# 8086-_Project.net
KiCad netlist of a schematic drawn in EasyEDA
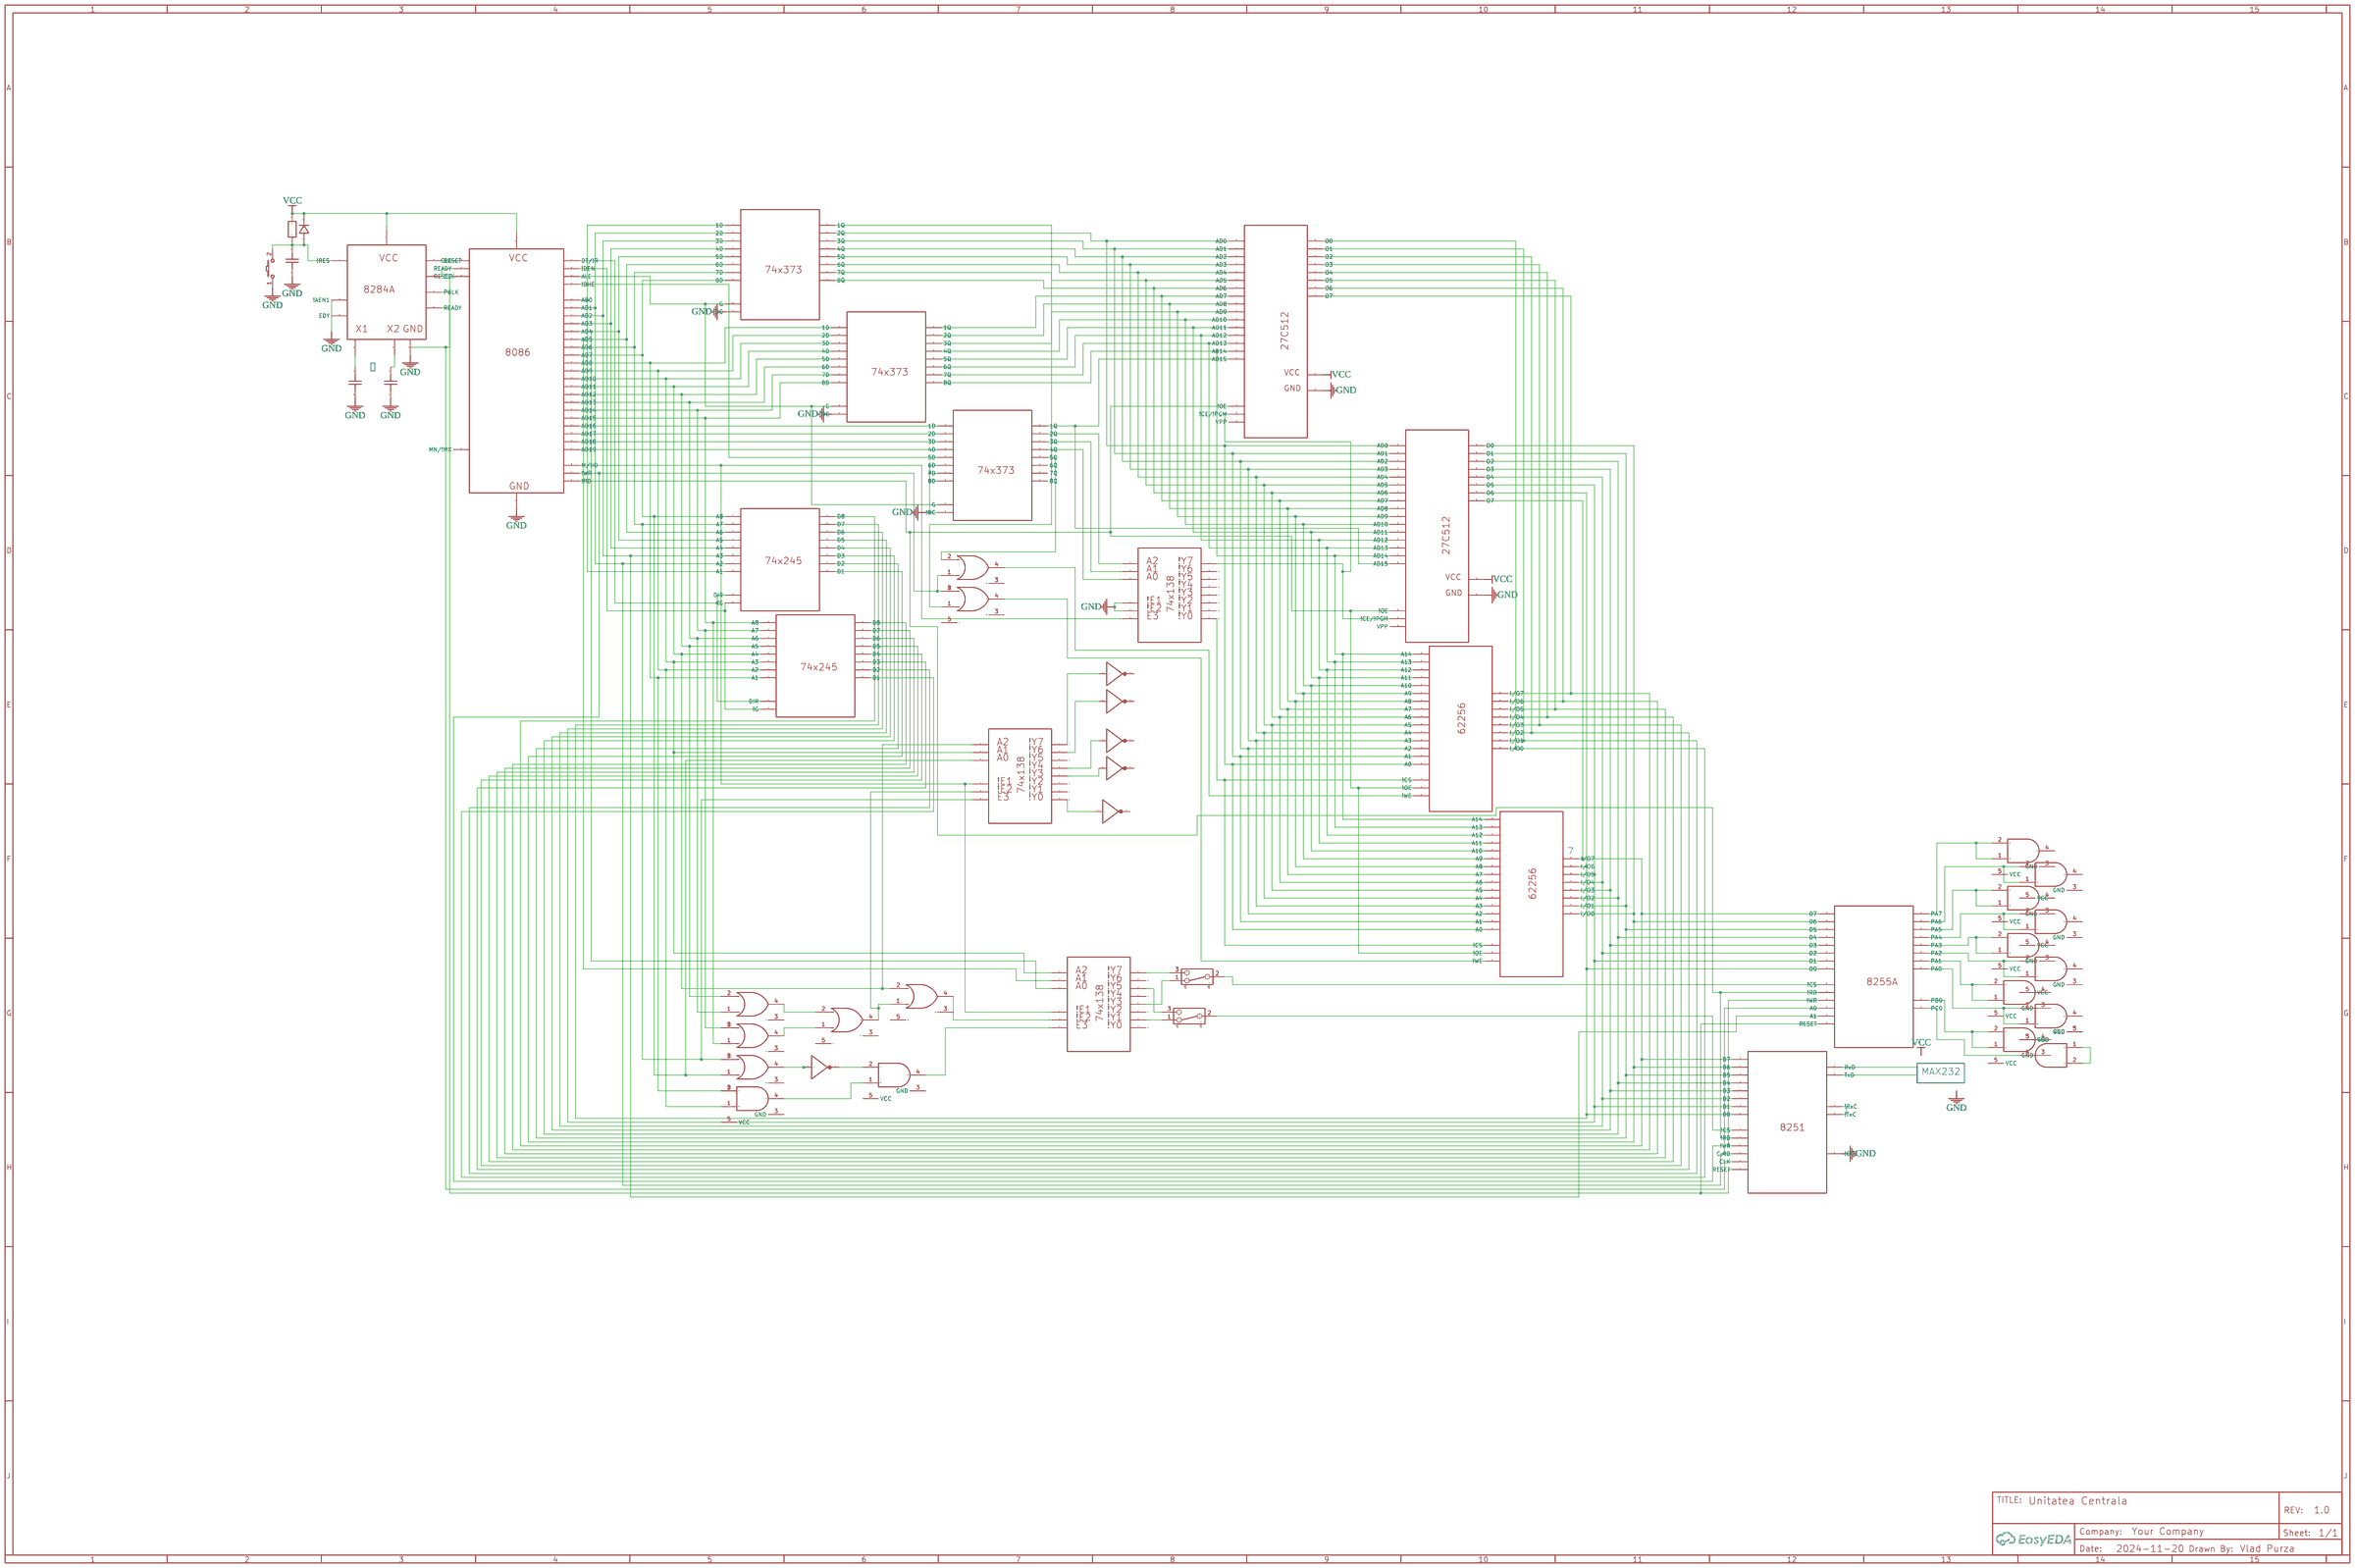
[diagram p0: schematic sheet]

(export (version "E")
  (design (tool "Eeschema 10.0.6"))
  (components
    (comp (ref "C1") (value "0.1u") (libsource (lib "") (part "C_0603_US")))
    (comp (ref "C2") (value "0.1u") (libsource (lib "") (part "C_0805_US")))
    (comp (ref "C3") (value "0.1u") (libsource (lib "") (part "C_0805_US")))
    (comp (ref "D1")
      (value "1N4007W")
      (fields (field (name "Manufacturer") "BLUE ROCKET"))
      (libsource (lib "") (part "1N4007W"))
    )
    (comp (ref "KEY1")
      (value "K2-3.6×6.1_SMD")
      (fields (field (name "Manufacturer Part") "K2-1107ST-A4SW-06"))
      (libsource (lib "") (part "K2-3.6×6.1_SMD"))
    )
    (comp (ref "R1") (value "1k") (libsource (lib "") (part "R_0603_EU")))
    (comp (ref "SW1")
      (value "SK-12D02-VG5")
      (fields (field (name "Manufacturer") "Rectangular Connectors - Contacts"))
      (libsource (lib "") (part "SK-12D02-VG5"))
    )
    (comp (ref "SW2")
      (value "SK-12D02-VG5")
      (fields (field (name "Manufacturer") "Rectangular Connectors - Contacts"))
      (libsource (lib "") (part "SK-12D02-VG5"))
    )
    (comp (ref "U1") (value "8086") (libsource (lib "") (part "8086")))
    (comp (ref "U2") (value "74x373") (libsource (lib "") (part "74x373")))
    (comp (ref "U3") (value "74x245") (libsource (lib "") (part "74x245")))
    (comp (ref "U4") (value "74x245") (libsource (lib "") (part "74x245")))
    (comp (ref "U5") (value "8284A") (libsource (lib "") (part "8284A")))
    (comp (ref "U6") (value "27C512") (libsource (lib "") (part "27C512")))
    (comp (ref "U7") (value "27C512") (libsource (lib "") (part "27C512")))
    (comp (ref "U8") (value "74x373") (libsource (lib "") (part "74x373")))
    (comp (ref "U9") (value "74x373") (libsource (lib "") (part "74x373")))
    (comp (ref "U10") (value "74x138") (libsource (lib "") (part "74x138")))
    (comp (ref "U11") (value "MC74VHC1G32DFT1") (libsource (lib "") (part "MC74VHC1G32DFT1")))
    (comp (ref "U12") (value "MC74VHC1G32DFT1") (libsource (lib "") (part "MC74VHC1G32DFT1")))
    (comp (ref "U13") (value "62256") (libsource (lib "") (part "62256")))
    (comp (ref "U14") (value "62256") (libsource (lib "") (part "62256")))
    (comp (ref "U15") (value "74x138") (libsource (lib "") (part "74x138")))
    (comp (ref "U16") (value "74x138") (libsource (lib "") (part "74x138")))
    (comp (ref "U17") (value "HD74ALVC1G08VS") (libsource (lib "") (part "HD74ALVC1G08VS")))
    (comp (ref "U18") (value "HD74ALVC1G08VS") (libsource (lib "") (part "HD74ALVC1G08VS")))
    (comp (ref "U19") (value "MC74VHC1G32DFT1") (libsource (lib "") (part "MC74VHC1G32DFT1_1")))
    (comp (ref "U20") (value "MC74VHC1G32DFT1") (libsource (lib "") (part "MC74VHC1G32DFT1_1")))
    (comp (ref "U21") (value "MC74VHC1G32DFT1") (libsource (lib "") (part "MC74VHC1G32DFT1_1")))
    (comp (ref "U22") (value "MC74VHC1G32DFT1") (libsource (lib "") (part "MC74VHC1G32DFT1_1")))
    (comp (ref "U23") (value "MC74VHC1G32DFT1") (libsource (lib "") (part "MC74VHC1G32DFT1_1")))
    (comp (ref "U24") (value "NOT Gate") (libsource (lib "") (part "NOT Gate")))
    (comp (ref "U25") (value "NOT Gate") (libsource (lib "") (part "NOT Gate")))
    (comp (ref "U26") (value "NOT Gate") (libsource (lib "") (part "NOT Gate")))
    (comp (ref "U27") (value "NOT Gate") (libsource (lib "") (part "NOT Gate")))
    (comp (ref "U28") (value "NOT Gate") (libsource (lib "") (part "NOT Gate")))
    (comp (ref "U29") (value "NOT Gate") (libsource (lib "") (part "NOT Gate")))
    (comp (ref "U30") (value "8251") (libsource (lib "") (part "8251")))
    (comp (ref "U31") (value "8255A") (libsource (lib "") (part "8255A")))
    (comp (ref "U32") (value "HD74ALVC1G08VS") (libsource (lib "") (part "HD74ALVC1G08VS")))
    (comp (ref "U33") (value "HD74ALVC1G08VS") (libsource (lib "") (part "HD74ALVC1G08VS")))
    (comp (ref "U34") (value "HD74ALVC1G08VS") (libsource (lib "") (part "HD74ALVC1G08VS")))
    (comp (ref "U35") (value "HD74ALVC1G08VS") (libsource (lib "") (part "HD74ALVC1G08VS")))
    (comp (ref "U36") (value "HD74ALVC1G08VS") (libsource (lib "") (part "HD74ALVC1G08VS")))
    (comp (ref "U37") (value "HD74ALVC1G08VS") (libsource (lib "") (part "HD74ALVC1G08VS")))
    (comp (ref "U38") (value "HD74ALVC1G08VS") (libsource (lib "") (part "HD74ALVC1G08VS")))
    (comp (ref "U39") (value "HD74ALVC1G08VS") (libsource (lib "") (part "HD74ALVC1G08VS")))
    (comp (ref "U40") (value "HD74ALVC1G08VS") (libsource (lib "") (part "HD74ALVC1G08VS")))
    (comp (ref "U41") (value "HD74ALVC1G08VS") (libsource (lib "") (part "HD74ALVC1G08VS_1")))
  )
  (nets
    (net (code "1") (name "GND") (class "Default")
      (node (ref "C1") (pin "2") (pinfunction "2_2") (pintype "unspecified"))
      (node (ref "C2") (pin "2") (pinfunction "2_2") (pintype "unspecified"))
      (node (ref "C3") (pin "2") (pinfunction "2_2") (pintype "unspecified"))
      (node (ref "KEY1") (pin "1") (pinfunction "1_1") (pintype "unspecified"))
    )
    (net (code "2") (name "Net-(C1-Pad1)") (class "Default")
      (node (ref "C1") (pin "1") (pinfunction "1_1") (pintype "unspecified"))
      (node (ref "D1") (pin "2") (pinfunction "2_2") (pintype "unspecified"))
      (node (ref "KEY1") (pin "2") (pinfunction "2_2") (pintype "unspecified"))
      (node (ref "R1") (pin "1") (pinfunction "1_1") (pintype "unspecified"))
    )
    (net (code "3") (name "Net-(U11-IN_A)") (class "Default")
      (node (ref "U11") (pin "2") (pinfunction "IN_A_2") (pintype "unspecified"))
      (node (ref "U12") (pin "1") (pinfunction "IN_B_1") (pintype "unspecified"))
      (node (ref "U12") (pin "5") (pinfunction "VDD_5") (pintype "passive"))
    )
    (net (code "4") (name "Net-(U17-IN_A)") (class "Default")
      (node (ref "U17") (pin "2") (pinfunction "IN_A_2") (pintype "unspecified"))
      (node (ref "U24") (pin "2") (pinfunction "OUT_2") (pintype "unspecified"))
    )
    (net (code "5") (name "Net-(U17-IN_B)") (class "Default")
      (node (ref "U17") (pin "1") (pinfunction "IN_B_1") (pintype "unspecified"))
      (node (ref "U18") (pin "4") (pinfunction "OUT_Y_4") (pintype "output"))
    )
    (net (code "6") (name "Net-(U18-IN_A)") (class "Default")
      (node (ref "U18") (pin "2") (pinfunction "IN_A_2") (pintype "unspecified"))
      (node (ref "U19") (pin "5") (pinfunction "VDD_5") (pintype "passive"))
    )
    (net (code "7") (name "Net-(U19-IN_A)") (class "Default")
      (node (ref "U19") (pin "2") (pinfunction "IN_A_2") (pintype "unspecified"))
      (node (ref "U20") (pin "5") (pinfunction "VDD_5") (pintype "passive"))
    )
    (net (code "8") (name "Net-(U19-Y)") (class "Default")
      (node (ref "U19") (pin "4") (pinfunction "Y_4") (pintype "output"))
      (node (ref "U24") (pin "1") (pinfunction "IN_1") (pintype "unspecified"))
    )
    (net (code "9") (name "Net-(U20-IN_A)") (class "Default")
      (node (ref "U20") (pin "2") (pinfunction "IN_A_2") (pintype "unspecified"))
      (node (ref "U21") (pin "5") (pinfunction "VDD_5") (pintype "passive"))
    )
    (net (code "10") (name "Net-(U20-Y)") (class "Default")
      (node (ref "U20") (pin "4") (pinfunction "Y_4") (pintype "output"))
      (node (ref "U22") (pin "1") (pinfunction "IN_B_1") (pintype "unspecified"))
    )
    (net (code "11") (name "Net-(U21-Y)") (class "Default")
      (node (ref "U21") (pin "4") (pinfunction "Y_4") (pintype "output"))
      (node (ref "U22") (pin "2") (pinfunction "IN_A_2") (pintype "unspecified"))
    )
    (net (code "12") (name "Net-(U22-Y)") (class "Default")
      (node (ref "U22") (pin "4") (pinfunction "Y_4") (pintype "output"))
      (node (ref "U23") (pin "1") (pinfunction "IN_B_1") (pintype "unspecified"))
    )
    (net (code "13") (name "Net-(U32-IN_A)") (class "Default")
      (node (ref "U32") (pin "1") (pinfunction "IN_B_1") (pintype "unspecified"))
      (node (ref "U32") (pin "2") (pinfunction "IN_A_2") (pintype "unspecified"))
    )
    (net (code "14") (name "Net-(U33-IN_A)") (class "Default")
      (node (ref "U33") (pin "1") (pinfunction "IN_B_1") (pintype "unspecified"))
      (node (ref "U33") (pin "2") (pinfunction "IN_A_2") (pintype "unspecified"))
    )
    (net (code "15") (name "Net-(U34-IN_A)") (class "Default")
      (node (ref "U34") (pin "1") (pinfunction "IN_B_1") (pintype "unspecified"))
      (node (ref "U34") (pin "2") (pinfunction "IN_A_2") (pintype "unspecified"))
    )
    (net (code "16") (name "Net-(U35-IN_A)") (class "Default")
      (node (ref "U35") (pin "1") (pinfunction "IN_B_1") (pintype "unspecified"))
      (node (ref "U35") (pin "2") (pinfunction "IN_A_2") (pintype "unspecified"))
    )
    (net (code "17") (name "Net-(U36-IN_A)") (class "Default")
      (node (ref "U36") (pin "1") (pinfunction "IN_B_1") (pintype "unspecified"))
      (node (ref "U36") (pin "2") (pinfunction "IN_A_2") (pintype "unspecified"))
    )
    (net (code "18") (name "Net-(U37-IN_A)") (class "Default")
      (node (ref "U37") (pin "1") (pinfunction "IN_B_1") (pintype "unspecified"))
      (node (ref "U37") (pin "2") (pinfunction "IN_A_2") (pintype "unspecified"))
    )
    (net (code "19") (name "Net-(U38-IN_A)") (class "Default")
      (node (ref "U38") (pin "1") (pinfunction "IN_B_1") (pintype "unspecified"))
      (node (ref "U38") (pin "2") (pinfunction "IN_A_2") (pintype "unspecified"))
    )
    (net (code "20") (name "Net-(U39-GND)") (class "Default")
      (node (ref "U39") (pin "3") (pinfunction "GND_3") (pintype "passive"))
      (node (ref "U41") (pin "5") (pinfunction "VCC_5") (pintype "passive"))
    )
    (net (code "21") (name "Net-(U39-IN_A)") (class "Default")
      (node (ref "U39") (pin "1") (pinfunction "IN_B_1") (pintype "unspecified"))
      (node (ref "U39") (pin "2") (pinfunction "IN_A_2") (pintype "unspecified"))
    )
    (net (code "22") (name "Net-(U39-VCC)") (class "Default")
      (node (ref "U39") (pin "5") (pinfunction "VCC_5") (pintype "passive"))
      (node (ref "U41") (pin "3") (pinfunction "GND_3") (pintype "passive"))
    )
    (net (code "23") (name "Net-(U40-IN_A)") (class "Default")
      (node (ref "U40") (pin "1") (pinfunction "IN_B_1") (pintype "unspecified"))
      (node (ref "U40") (pin "2") (pinfunction "IN_A_2") (pintype "unspecified"))
    )
    (net (code "24") (name "Net-(U41-IN_A)") (class "Default")
      (node (ref "U41") (pin "1") (pinfunction "IN_B_1") (pintype "unspecified"))
      (node (ref "U41") (pin "2") (pinfunction "IN_A_2") (pintype "unspecified"))
    )
    (net (code "25") (name "VCC") (class "Default")
      (node (ref "D1") (pin "1") (pinfunction "1_1") (pintype "unspecified"))
      (node (ref "R1") (pin "2") (pinfunction "2_2") (pintype "unspecified"))
    )
    (net (code "26") (name "unconnected-(C2-Pad1)") (class "Default")
      (node (ref "C2") (pin "1") (pinfunction "1_1") (pintype "unspecified"))
    )
    (net (code "27") (name "unconnected-(C3-Pad1)") (class "Default")
      (node (ref "C3") (pin "1") (pinfunction "1_1") (pintype "unspecified"))
    )
    (net (code "28") (name "unconnected-(SW1-Pad1)") (class "Default")
      (node (ref "SW1") (pin "1") (pinfunction "1_1") (pintype "unspecified"))
    )
    (net (code "29") (name "unconnected-(SW1-Pad2)") (class "Default")
      (node (ref "SW1") (pin "2") (pinfunction "2_2") (pintype "unspecified"))
    )
    (net (code "30") (name "unconnected-(SW1-Pad3)") (class "Default")
      (node (ref "SW1") (pin "3") (pinfunction "3_3") (pintype "unspecified"))
    )
    (net (code "31") (name "unconnected-(SW1-Pad4)") (class "Default")
      (node (ref "SW1") (pin "4") (pinfunction "4_4") (pintype "unspecified"))
    )
    (net (code "32") (name "unconnected-(SW1-Pad5)") (class "Default")
      (node (ref "SW1") (pin "5") (pinfunction "5_5") (pintype "unspecified"))
    )
    (net (code "33") (name "unconnected-(SW2-Pad1)") (class "Default")
      (node (ref "SW2") (pin "1") (pinfunction "1_1") (pintype "unspecified"))
    )
    (net (code "34") (name "unconnected-(SW2-Pad2)") (class "Default")
      (node (ref "SW2") (pin "2") (pinfunction "2_2") (pintype "unspecified"))
    )
    (net (code "35") (name "unconnected-(SW2-Pad3)") (class "Default")
      (node (ref "SW2") (pin "3") (pinfunction "3_3") (pintype "unspecified"))
    )
    (net (code "36") (name "unconnected-(SW2-Pad4)") (class "Default")
      (node (ref "SW2") (pin "4") (pinfunction "4_4") (pintype "unspecified"))
    )
    (net (code "37") (name "unconnected-(SW2-Pad5)") (class "Default")
      (node (ref "SW2") (pin "5") (pinfunction "5_5") (pintype "unspecified"))
    )
    (net (code "38") (name "unconnected-(U1-!BHE-Pad23)") (class "Default")
      (node (ref "U1") (pin "23") (pinfunction "!BHE_23") (pintype "unspecified"))
    )
    (net (code "39") (name "unconnected-(U1-!DEN-Pad21)") (class "Default")
      (node (ref "U1") (pin "21") (pinfunction "!DEN_21") (pintype "unspecified"))
    )
    (net (code "40") (name "unconnected-(U1-!RD-Pad30)") (class "Default")
      (node (ref "U1") (pin "30") (pinfunction "!RD_30") (pintype "unspecified"))
    )
    (net (code "41") (name "unconnected-(U1-!WR-Pad29)") (class "Default")
      (node (ref "U1") (pin "29") (pinfunction "!WR_29") (pintype "unspecified"))
    )
    (net (code "42") (name "unconnected-(U1-20-Pad31)") (class "Default")
      (node (ref "U1") (pin "31") (pinfunction "20_31") (pintype "unspecified"))
    )
    (net (code "43") (name "unconnected-(U1-21-Pad32)") (class "Default")
      (node (ref "U1") (pin "32") (pinfunction "21_32") (pintype "unspecified"))
    )
    (net (code "44") (name "unconnected-(U1-AD0-Pad0)") (class "Default")
      (node (ref "U1") (pin "0") (pinfunction "AD0_0") (pintype "unspecified"))
    )
    (net (code "45") (name "unconnected-(U1-AD1-Pad1)") (class "Default")
      (node (ref "U1") (pin "1") (pinfunction "AD1_1") (pintype "unspecified"))
    )
    (net (code "46") (name "unconnected-(U1-AD2-Pad2)") (class "Default")
      (node (ref "U1") (pin "2") (pinfunction "AD2_2") (pintype "unspecified"))
    )
    (net (code "47") (name "unconnected-(U1-AD3-Pad3)") (class "Default")
      (node (ref "U1") (pin "3") (pinfunction "AD3_3") (pintype "unspecified"))
    )
    (net (code "48") (name "unconnected-(U1-AD4-Pad4)") (class "Default")
      (node (ref "U1") (pin "4") (pinfunction "AD4_4") (pintype "unspecified"))
    )
    (net (code "49") (name "unconnected-(U1-AD5-Pad5)") (class "Default")
      (node (ref "U1") (pin "5") (pinfunction "AD5_5") (pintype "unspecified"))
    )
    (net (code "50") (name "unconnected-(U1-AD6-Pad6)") (class "Default")
      (node (ref "U1") (pin "6") (pinfunction "AD6_6") (pintype "unspecified"))
    )
    (net (code "51") (name "unconnected-(U1-AD7-Pad7)") (class "Default")
      (node (ref "U1") (pin "7") (pinfunction "AD7_7") (pintype "unspecified"))
    )
    (net (code "52") (name "unconnected-(U1-AD8-Pad8)") (class "Default")
      (node (ref "U1") (pin "8") (pinfunction "AD8_8") (pintype "unspecified"))
    )
    (net (code "53") (name "unconnected-(U1-AD9-Pad9)") (class "Default")
      (node (ref "U1") (pin "9") (pinfunction "AD9_9") (pintype "unspecified"))
    )
    (net (code "54") (name "unconnected-(U1-AD10-Pad10)") (class "Default")
      (node (ref "U1") (pin "10") (pinfunction "AD10_10") (pintype "unspecified"))
    )
    (net (code "55") (name "unconnected-(U1-AD11-Pad11)") (class "Default")
      (node (ref "U1") (pin "11") (pinfunction "AD11_11") (pintype "unspecified"))
    )
    (net (code "56") (name "unconnected-(U1-AD12-Pad12)") (class "Default")
      (node (ref "U1") (pin "12") (pinfunction "AD12_12") (pintype "unspecified"))
    )
    (net (code "57") (name "unconnected-(U1-AD13-Pad13)") (class "Default")
      (node (ref "U1") (pin "13") (pinfunction "AD13_13") (pintype "unspecified"))
    )
    (net (code "58") (name "unconnected-(U1-AD14-Pad14)") (class "Default")
      (node (ref "U1") (pin "14") (pinfunction "AD14_14") (pintype "unspecified"))
    )
    (net (code "59") (name "unconnected-(U1-AD15-Pad15)") (class "Default")
      (node (ref "U1") (pin "15") (pinfunction "AD15_15") (pintype "unspecified"))
    )
    (net (code "60") (name "unconnected-(U1-AD16-Pad16)") (class "Default")
      (node (ref "U1") (pin "16") (pinfunction "AD16_16") (pintype "unspecified"))
    )
    (net (code "61") (name "unconnected-(U1-AD17-Pad17)") (class "Default")
      (node (ref "U1") (pin "17") (pinfunction "AD17_17") (pintype "unspecified"))
    )
    (net (code "62") (name "unconnected-(U1-AD18-Pad18)") (class "Default")
      (node (ref "U1") (pin "18") (pinfunction "AD18_18") (pintype "unspecified"))
    )
    (net (code "63") (name "unconnected-(U1-AD19-Pad19)") (class "Default")
      (node (ref "U1") (pin "19") (pinfunction "AD19_19") (pintype "unspecified"))
    )
    (net (code "64") (name "unconnected-(U1-ALE-Pad22)") (class "Default")
      (node (ref "U1") (pin "22") (pinfunction "ALE_22") (pintype "unspecified"))
    )
    (net (code "65") (name "unconnected-(U1-CLK-Pad24)") (class "Default")
      (node (ref "U1") (pin "24") (pinfunction "CLK_24") (pintype "unspecified"))
    )
    (net (code "66") (name "unconnected-(U1-DT{slash}!R-Pad20)") (class "Default")
      (node (ref "U1") (pin "20") (pinfunction "DT/!R_20") (pintype "unspecified"))
    )
    (net (code "67") (name "unconnected-(U1-MN{slash}!MX-Pad27)") (class "Default")
      (node (ref "U1") (pin "27") (pinfunction "MN/!MX_27") (pintype "unspecified"))
    )
    (net (code "68") (name "unconnected-(U1-M{slash}!IO-Pad28)") (class "Default")
      (node (ref "U1") (pin "28") (pinfunction "M/!IO_28") (pintype "unspecified"))
    )
    (net (code "69") (name "unconnected-(U1-READY-Pad25)") (class "Default")
      (node (ref "U1") (pin "25") (pinfunction "READY_25") (pintype "unspecified"))
    )
    (net (code "70") (name "unconnected-(U1-RESET-Pad26)") (class "Default")
      (node (ref "U1") (pin "26") (pinfunction "RESET_26") (pintype "unspecified"))
    )
    (net (code "71") (name "unconnected-(U2-!OC-Pad21)") (class "Default")
      (node (ref "U2") (pin "21") (pinfunction "!OC_21") (pintype "unspecified"))
    )
    (net (code "72") (name "unconnected-(U2-1D-Pad1)") (class "Default")
      (node (ref "U2") (pin "1") (pinfunction "1D_1") (pintype "unspecified"))
    )
    (net (code "73") (name "unconnected-(U2-1Q-Pad9)") (class "Default")
      (node (ref "U2") (pin "9") (pinfunction "1Q_9") (pintype "unspecified"))
    )
    (net (code "74") (name "unconnected-(U2-2D-Pad2)") (class "Default")
      (node (ref "U2") (pin "2") (pinfunction "2D_2") (pintype "unspecified"))
    )
    (net (code "75") (name "unconnected-(U2-2Q-Pad10)") (class "Default")
      (node (ref "U2") (pin "10") (pinfunction "2Q_10") (pintype "unspecified"))
    )
    (net (code "76") (name "unconnected-(U2-3D-Pad3)") (class "Default")
      (node (ref "U2") (pin "3") (pinfunction "3D_3") (pintype "unspecified"))
    )
    (net (code "77") (name "unconnected-(U2-3Q-Pad11)") (class "Default")
      (node (ref "U2") (pin "11") (pinfunction "3Q_11") (pintype "unspecified"))
    )
    (net (code "78") (name "unconnected-(U2-4D-Pad4)") (class "Default")
      (node (ref "U2") (pin "4") (pinfunction "4D_4") (pintype "unspecified"))
    )
    (net (code "79") (name "unconnected-(U2-4Q-Pad12)") (class "Default")
      (node (ref "U2") (pin "12") (pinfunction "4Q_12") (pintype "unspecified"))
    )
    (net (code "80") (name "unconnected-(U2-5D-Pad5)") (class "Default")
      (node (ref "U2") (pin "5") (pinfunction "5D_5") (pintype "unspecified"))
    )
    (net (code "81") (name "unconnected-(U2-5Q-Pad16)") (class "Default")
      (node (ref "U2") (pin "16") (pinfunction "5Q_16") (pintype "unspecified"))
    )
    (net (code "82") (name "unconnected-(U2-6D-Pad6)") (class "Default")
      (node (ref "U2") (pin "6") (pinfunction "6D_6") (pintype "unspecified"))
    )
    (net (code "83") (name "unconnected-(U2-6Q-Pad13)") (class "Default")
      (node (ref "U2") (pin "13") (pinfunction "6Q_13") (pintype "unspecified"))
    )
    (net (code "84") (name "unconnected-(U2-7D-Pad7)") (class "Default")
      (node (ref "U2") (pin "7") (pinfunction "7D_7") (pintype "unspecified"))
    )
    (net (code "85") (name "unconnected-(U2-7Q-Pad14)") (class "Default")
      (node (ref "U2") (pin "14") (pinfunction "7Q_14") (pintype "unspecified"))
    )
    (net (code "86") (name "unconnected-(U2-8D-Pad8)") (class "Default")
      (node (ref "U2") (pin "8") (pinfunction "8D_8") (pintype "unspecified"))
    )
    (net (code "87") (name "unconnected-(U2-8Q-Pad15)") (class "Default")
      (node (ref "U2") (pin "15") (pinfunction "8Q_15") (pintype "unspecified"))
    )
    (net (code "88") (name "unconnected-(U2-G-Pad20)") (class "Default")
      (node (ref "U2") (pin "20") (pinfunction "G_20") (pintype "unspecified"))
    )
    (net (code "89") (name "unconnected-(U3-!G-Pad21)") (class "Default")
      (node (ref "U3") (pin "21") (pinfunction "!G_21") (pintype "unspecified"))
    )
    (net (code "90") (name "unconnected-(U3-A1-Pad8)") (class "Default")
      (node (ref "U3") (pin "8") (pinfunction "A1_8") (pintype "unspecified"))
    )
    (net (code "91") (name "unconnected-(U3-A2-Pad7)") (class "Default")
      (node (ref "U3") (pin "7") (pinfunction "A2_7") (pintype "unspecified"))
    )
    (net (code "92") (name "unconnected-(U3-A3-Pad6)") (class "Default")
      (node (ref "U3") (pin "6") (pinfunction "A3_6") (pintype "unspecified"))
    )
    (net (code "93") (name "unconnected-(U3-A4-Pad5)") (class "Default")
      (node (ref "U3") (pin "5") (pinfunction "A4_5") (pintype "unspecified"))
    )
    (net (code "94") (name "unconnected-(U3-A5-Pad4)") (class "Default")
      (node (ref "U3") (pin "4") (pinfunction "A5_4") (pintype "unspecified"))
    )
    (net (code "95") (name "unconnected-(U3-A6-Pad3)") (class "Default")
      (node (ref "U3") (pin "3") (pinfunction "A6_3") (pintype "unspecified"))
    )
    (net (code "96") (name "unconnected-(U3-A7-Pad2)") (class "Default")
      (node (ref "U3") (pin "2") (pinfunction "A7_2") (pintype "unspecified"))
    )
    (net (code "97") (name "unconnected-(U3-A8-Pad1)") (class "Default")
      (node (ref "U3") (pin "1") (pinfunction "A8_1") (pintype "unspecified"))
    )
    (net (code "98") (name "unconnected-(U3-D1-Pad15)") (class "Default")
      (node (ref "U3") (pin "15") (pinfunction "D1_15") (pintype "unspecified"))
    )
    (net (code "99") (name "unconnected-(U3-D2-Pad14)") (class "Default")
      (node (ref "U3") (pin "14") (pinfunction "D2_14") (pintype "unspecified"))
    )
    (net (code "100") (name "unconnected-(U3-D3-Pad13)") (class "Default")
      (node (ref "U3") (pin "13") (pinfunction "D3_13") (pintype "unspecified"))
    )
    (net (code "101") (name "unconnected-(U3-D4-Pad16)") (class "Default")
      (node (ref "U3") (pin "16") (pinfunction "D4_16") (pintype "unspecified"))
    )
    (net (code "102") (name "unconnected-(U3-D5-Pad12)") (class "Default")
      (node (ref "U3") (pin "12") (pinfunction "D5_12") (pintype "unspecified"))
    )
    (net (code "103") (name "unconnected-(U3-D6-Pad11)") (class "Default")
      (node (ref "U3") (pin "11") (pinfunction "D6_11") (pintype "unspecified"))
    )
    (net (code "104") (name "unconnected-(U3-D7-Pad10)") (class "Default")
      (node (ref "U3") (pin "10") (pinfunction "D7_10") (pintype "unspecified"))
    )
    (net (code "105") (name "unconnected-(U3-D8-Pad9)") (class "Default")
      (node (ref "U3") (pin "9") (pinfunction "D8_9") (pintype "unspecified"))
    )
    (net (code "106") (name "unconnected-(U3-DIR-Pad20)") (class "Default")
      (node (ref "U3") (pin "20") (pinfunction "DIR_20") (pintype "unspecified"))
    )
    (net (code "107") (name "unconnected-(U4-!G-Pad21)") (class "Default")
      (node (ref "U4") (pin "21") (pinfunction "!G_21") (pintype "unspecified"))
    )
    (net (code "108") (name "unconnected-(U4-A1-Pad8)") (class "Default")
      (node (ref "U4") (pin "8") (pinfunction "A1_8") (pintype "unspecified"))
    )
    (net (code "109") (name "unconnected-(U4-A2-Pad7)") (class "Default")
      (node (ref "U4") (pin "7") (pinfunction "A2_7") (pintype "unspecified"))
    )
    (net (code "110") (name "unconnected-(U4-A3-Pad6)") (class "Default")
      (node (ref "U4") (pin "6") (pinfunction "A3_6") (pintype "unspecified"))
    )
    (net (code "111") (name "unconnected-(U4-A4-Pad5)") (class "Default")
      (node (ref "U4") (pin "5") (pinfunction "A4_5") (pintype "unspecified"))
    )
    (net (code "112") (name "unconnected-(U4-A5-Pad4)") (class "Default")
      (node (ref "U4") (pin "4") (pinfunction "A5_4") (pintype "unspecified"))
    )
    (net (code "113") (name "unconnected-(U4-A6-Pad3)") (class "Default")
      (node (ref "U4") (pin "3") (pinfunction "A6_3") (pintype "unspecified"))
    )
    (net (code "114") (name "unconnected-(U4-A7-Pad2)") (class "Default")
      (node (ref "U4") (pin "2") (pinfunction "A7_2") (pintype "unspecified"))
    )
    (net (code "115") (name "unconnected-(U4-A8-Pad1)") (class "Default")
      (node (ref "U4") (pin "1") (pinfunction "A8_1") (pintype "unspecified"))
    )
    (net (code "116") (name "unconnected-(U4-D1-Pad15)") (class "Default")
      (node (ref "U4") (pin "15") (pinfunction "D1_15") (pintype "unspecified"))
    )
    (net (code "117") (name "unconnected-(U4-D2-Pad14)") (class "Default")
      (node (ref "U4") (pin "14") (pinfunction "D2_14") (pintype "unspecified"))
    )
    (net (code "118") (name "unconnected-(U4-D3-Pad13)") (class "Default")
      (node (ref "U4") (pin "13") (pinfunction "D3_13") (pintype "unspecified"))
    )
    (net (code "119") (name "unconnected-(U4-D4-Pad16)") (class "Default")
      (node (ref "U4") (pin "16") (pinfunction "D4_16") (pintype "unspecified"))
    )
    (net (code "120") (name "unconnected-(U4-D5-Pad12)") (class "Default")
      (node (ref "U4") (pin "12") (pinfunction "D5_12") (pintype "unspecified"))
    )
    (net (code "121") (name "unconnected-(U4-D6-Pad11)") (class "Default")
      (node (ref "U4") (pin "11") (pinfunction "D6_11") (pintype "unspecified"))
    )
    (net (code "122") (name "unconnected-(U4-D7-Pad10)") (class "Default")
      (node (ref "U4") (pin "10") (pinfunction "D7_10") (pintype "unspecified"))
    )
    (net (code "123") (name "unconnected-(U4-D8-Pad9)") (class "Default")
      (node (ref "U4") (pin "9") (pinfunction "D8_9") (pintype "unspecified"))
    )
    (net (code "124") (name "unconnected-(U4-DIR-Pad20)") (class "Default")
      (node (ref "U4") (pin "20") (pinfunction "DIR_20") (pintype "unspecified"))
    )
    (net (code "125") (name "unconnected-(U5-!AEN1-Pad5)") (class "Default")
      (node (ref "U5") (pin "5") (pinfunction "!AEN1_5") (pintype "unspecified"))
    )
    (net (code "126") (name "unconnected-(U5-!RES-Pad4)") (class "Default")
      (node (ref "U5") (pin "4") (pinfunction "!RES_4") (pintype "unspecified"))
    )
    (net (code "127") (name "unconnected-(U5-2-Pad7)") (class "Default")
      (node (ref "U5") (pin "7") (pinfunction "2_7") (pintype "unspecified"))
    )
    (net (code "128") (name "unconnected-(U5-3-Pad8)") (class "Default")
      (node (ref "U5") (pin "8") (pinfunction "3_8") (pintype "unspecified"))
    )
    (net (code "129") (name "unconnected-(U5-4-Pad9)") (class "Default")
      (node (ref "U5") (pin "9") (pinfunction "4_9") (pintype "unspecified"))
    )
    (net (code "130") (name "unconnected-(U5-5-Pad10)") (class "Default")
      (node (ref "U5") (pin "10") (pinfunction "5_10") (pintype "unspecified"))
    )
    (net (code "131") (name "unconnected-(U5-CLK-Pad1)") (class "Default")
      (node (ref "U5") (pin "1") (pinfunction "CLK_1") (pintype "unspecified"))
    )
    (net (code "132") (name "unconnected-(U5-EDY-Pad6)") (class "Default")
      (node (ref "U5") (pin "6") (pinfunction "EDY_6") (pintype "unspecified"))
    )
    (net (code "133") (name "unconnected-(U5-PCLK-Pad2)") (class "Default")
      (node (ref "U5") (pin "2") (pinfunction "PCLK_2") (pintype "unspecified"))
    )
    (net (code "134") (name "unconnected-(U5-READY-Pad3)") (class "Default")
      (node (ref "U5") (pin "3") (pinfunction "READY_3") (pintype "unspecified"))
    )
    (net (code "135") (name "unconnected-(U5-RESET-Pad0)") (class "Default")
      (node (ref "U5") (pin "0") (pinfunction "RESET_0") (pintype "unspecified"))
    )
    (net (code "136") (name "unconnected-(U6-!CE{slash}!PGM-Pad61)") (class "Default")
      (node (ref "U6") (pin "61") (pinfunction "!CE/!PGM_61") (pintype "unspecified"))
    )
    (net (code "137") (name "unconnected-(U6-!OE-Pad62)") (class "Default")
      (node (ref "U6") (pin "62") (pinfunction "!OE_62") (pintype "unspecified"))
    )
    (net (code "138") (name "unconnected-(U6-20-Pad31)") (class "Default")
      (node (ref "U6") (pin "31") (pinfunction "20_31") (pintype "unspecified"))
    )
    (net (code "139") (name "unconnected-(U6-21-Pad32)") (class "Default")
      (node (ref "U6") (pin "32") (pinfunction "21_32") (pintype "unspecified"))
    )
    (net (code "140") (name "unconnected-(U6-AD0-Pad0)") (class "Default")
      (node (ref "U6") (pin "0") (pinfunction "AD0_0") (pintype "unspecified"))
    )
    (net (code "141") (name "unconnected-(U6-AD1-Pad1)") (class "Default")
      (node (ref "U6") (pin "1") (pinfunction "AD1_1") (pintype "unspecified"))
    )
    (net (code "142") (name "unconnected-(U6-AD2-Pad2)") (class "Default")
      (node (ref "U6") (pin "2") (pinfunction "AD2_2") (pintype "unspecified"))
    )
    (net (code "143") (name "unconnected-(U6-AD3-Pad3)") (class "Default")
      (node (ref "U6") (pin "3") (pinfunction "AD3_3") (pintype "unspecified"))
    )
    (net (code "144") (name "unconnected-(U6-AD4-Pad4)") (class "Default")
      (node (ref "U6") (pin "4") (pinfunction "AD4_4") (pintype "unspecified"))
    )
    (net (code "145") (name "unconnected-(U6-AD5-Pad5)") (class "Default")
      (node (ref "U6") (pin "5") (pinfunction "AD5_5") (pintype "unspecified"))
    )
    (net (code "146") (name "unconnected-(U6-AD6-Pad6)") (class "Default")
      (node (ref "U6") (pin "6") (pinfunction "AD6_6") (pintype "unspecified"))
    )
    (net (code "147") (name "unconnected-(U6-AD7-Pad7)") (class "Default")
      (node (ref "U6") (pin "7") (pinfunction "AD7_7") (pintype "unspecified"))
    )
    (net (code "148") (name "unconnected-(U6-AD8-Pad8)") (class "Default")
      (node (ref "U6") (pin "8") (pinfunction "AD8_8") (pintype "unspecified"))
    )
    (net (code "149") (name "unconnected-(U6-AD9-Pad9)") (class "Default")
      (node (ref "U6") (pin "9") (pinfunction "AD9_9") (pintype "unspecified"))
    )
    (net (code "150") (name "unconnected-(U6-AD10-Pad10)") (class "Default")
      (node (ref "U6") (pin "10") (pinfunction "AD10_10") (pintype "unspecified"))
    )
    (net (code "151") (name "unconnected-(U6-AD11-Pad11)") (class "Default")
      (node (ref "U6") (pin "11") (pinfunction "AD11_11") (pintype "unspecified"))
    )
    (net (code "152") (name "unconnected-(U6-AD12-Pad12)") (class "Default")
      (node (ref "U6") (pin "12") (pinfunction "AD12_12") (pintype "unspecified"))
    )
    (net (code "153") (name "unconnected-(U6-AD13-Pad13)") (class "Default")
      (node (ref "U6") (pin "13") (pinfunction "AD13_13") (pintype "unspecified"))
    )
    (net (code "154") (name "unconnected-(U6-AD14-Pad14)") (class "Default")
      (node (ref "U6") (pin "14") (pinfunction "AD14_14") (pintype "unspecified"))
    )
    (net (code "155") (name "unconnected-(U6-AD15-Pad63)") (class "Default")
      (node (ref "U6") (pin "63") (pinfunction "AD15_63") (pintype "unspecified"))
    )
    (net (code "156") (name "unconnected-(U6-O0-Pad50)") (class "Default")
      (node (ref "U6") (pin "50") (pinfunction "O0_50") (pintype "unspecified"))
    )
    (net (code "157") (name "unconnected-(U6-O1-Pad51)") (class "Default")
      (node (ref "U6") (pin "51") (pinfunction "O1_51") (pintype "unspecified"))
    )
    (net (code "158") (name "unconnected-(U6-O2-Pad52)") (class "Default")
      (node (ref "U6") (pin "52") (pinfunction "O2_52") (pintype "unspecified"))
    )
    (net (code "159") (name "unconnected-(U6-O3-Pad53)") (class "Default")
      (node (ref "U6") (pin "53") (pinfunction "O3_53") (pintype "unspecified"))
    )
    (net (code "160") (name "unconnected-(U6-O4-Pad54)") (class "Default")
      (node (ref "U6") (pin "54") (pinfunction "O4_54") (pintype "unspecified"))
    )
    (net (code "161") (name "unconnected-(U6-O5-Pad55)") (class "Default")
      (node (ref "U6") (pin "55") (pinfunction "O5_55") (pintype "unspecified"))
    )
    (net (code "162") (name "unconnected-(U6-O6-Pad56)") (class "Default")
      (node (ref "U6") (pin "56") (pinfunction "O6_56") (pintype "unspecified"))
    )
    (net (code "163") (name "unconnected-(U6-O7-Pad57)") (class "Default")
      (node (ref "U6") (pin "57") (pinfunction "O7_57") (pintype "unspecified"))
    )
    (net (code "164") (name "unconnected-(U6-VPP-Pad60)") (class "Default")
      (node (ref "U6") (pin "60") (pinfunction "VPP_60") (pintype "unspecified"))
    )
    (net (code "165") (name "unconnected-(U7-!CE{slash}!PGM-Pad61)") (class "Default")
      (node (ref "U7") (pin "61") (pinfunction "!CE/!PGM_61") (pintype "unspecified"))
    )
    (net (code "166") (name "unconnected-(U7-!OE-Pad62)") (class "Default")
      (node (ref "U7") (pin "62") (pinfunction "!OE_62") (pintype "unspecified"))
    )
    (net (code "167") (name "unconnected-(U7-20-Pad31)") (class "Default")
      (node (ref "U7") (pin "31") (pinfunction "20_31") (pintype "unspecified"))
    )
    (net (code "168") (name "unconnected-(U7-21-Pad32)") (class "Default")
      (node (ref "U7") (pin "32") (pinfunction "21_32") (pintype "unspecified"))
    )
    (net (code "169") (name "unconnected-(U7-AD0-Pad0)") (class "Default")
      (node (ref "U7") (pin "0") (pinfunction "AD0_0") (pintype "unspecified"))
    )
    (net (code "170") (name "unconnected-(U7-AD1-Pad1)") (class "Default")
      (node (ref "U7") (pin "1") (pinfunction "AD1_1") (pintype "unspecified"))
    )
    (net (code "171") (name "unconnected-(U7-AD2-Pad2)") (class "Default")
      (node (ref "U7") (pin "2") (pinfunction "AD2_2") (pintype "unspecified"))
    )
    (net (code "172") (name "unconnected-(U7-AD3-Pad3)") (class "Default")
      (node (ref "U7") (pin "3") (pinfunction "AD3_3") (pintype "unspecified"))
    )
    (net (code "173") (name "unconnected-(U7-AD4-Pad4)") (class "Default")
      (node (ref "U7") (pin "4") (pinfunction "AD4_4") (pintype "unspecified"))
    )
    (net (code "174") (name "unconnected-(U7-AD5-Pad5)") (class "Default")
      (node (ref "U7") (pin "5") (pinfunction "AD5_5") (pintype "unspecified"))
    )
    (net (code "175") (name "unconnected-(U7-AD6-Pad6)") (class "Default")
      (node (ref "U7") (pin "6") (pinfunction "AD6_6") (pintype "unspecified"))
    )
    (net (code "176") (name "unconnected-(U7-AD7-Pad7)") (class "Default")
      (node (ref "U7") (pin "7") (pinfunction "AD7_7") (pintype "unspecified"))
    )
    (net (code "177") (name "unconnected-(U7-AD8-Pad8)") (class "Default")
      (node (ref "U7") (pin "8") (pinfunction "AD8_8") (pintype "unspecified"))
    )
    (net (code "178") (name "unconnected-(U7-AD9-Pad9)") (class "Default")
      (node (ref "U7") (pin "9") (pinfunction "AD9_9") (pintype "unspecified"))
    )
    (net (code "179") (name "unconnected-(U7-AD10-Pad10)") (class "Default")
      (node (ref "U7") (pin "10") (pinfunction "AD10_10") (pintype "unspecified"))
    )
    (net (code "180") (name "unconnected-(U7-AD11-Pad11)") (class "Default")
      (node (ref "U7") (pin "11") (pinfunction "AD11_11") (pintype "unspecified"))
    )
    (net (code "181") (name "unconnected-(U7-AD12-Pad12)") (class "Default")
      (node (ref "U7") (pin "12") (pinfunction "AD12_12") (pintype "unspecified"))
    )
    (net (code "182") (name "unconnected-(U7-AD13-Pad13)") (class "Default")
      (node (ref "U7") (pin "13") (pinfunction "AD13_13") (pintype "unspecified"))
    )
    (net (code "183") (name "unconnected-(U7-AD14-Pad14)") (class "Default")
      (node (ref "U7") (pin "14") (pinfunction "AD14_14") (pintype "unspecified"))
    )
    (net (code "184") (name "unconnected-(U7-AD15-Pad63)") (class "Default")
      (node (ref "U7") (pin "63") (pinfunction "AD15_63") (pintype "unspecified"))
    )
    (net (code "185") (name "unconnected-(U7-O0-Pad50)") (class "Default")
      (node (ref "U7") (pin "50") (pinfunction "O0_50") (pintype "unspecified"))
    )
    (net (code "186") (name "unconnected-(U7-O1-Pad51)") (class "Default")
      (node (ref "U7") (pin "51") (pinfunction "O1_51") (pintype "unspecified"))
    )
    (net (code "187") (name "unconnected-(U7-O2-Pad52)") (class "Default")
      (node (ref "U7") (pin "52") (pinfunction "O2_52") (pintype "unspecified"))
    )
    (net (code "188") (name "unconnected-(U7-O3-Pad53)") (class "Default")
      (node (ref "U7") (pin "53") (pinfunction "O3_53") (pintype "unspecified"))
    )
    (net (code "189") (name "unconnected-(U7-O4-Pad54)") (class "Default")
      (node (ref "U7") (pin "54") (pinfunction "O4_54") (pintype "unspecified"))
    )
    (net (code "190") (name "unconnected-(U7-O5-Pad55)") (class "Default")
      (node (ref "U7") (pin "55") (pinfunction "O5_55") (pintype "unspecified"))
    )
    (net (code "191") (name "unconnected-(U7-O6-Pad56)") (class "Default")
      (node (ref "U7") (pin "56") (pinfunction "O6_56") (pintype "unspecified"))
    )
    (net (code "192") (name "unconnected-(U7-O7-Pad57)") (class "Default")
      (node (ref "U7") (pin "57") (pinfunction "O7_57") (pintype "unspecified"))
    )
    (net (code "193") (name "unconnected-(U7-VPP-Pad60)") (class "Default")
      (node (ref "U7") (pin "60") (pinfunction "VPP_60") (pintype "unspecified"))
    )
    (net (code "194") (name "unconnected-(U8-!OC-Pad21)") (class "Default")
      (node (ref "U8") (pin "21") (pinfunction "!OC_21") (pintype "unspecified"))
    )
    (net (code "195") (name "unconnected-(U8-1D-Pad1)") (class "Default")
      (node (ref "U8") (pin "1") (pinfunction "1D_1") (pintype "unspecified"))
    )
    (net (code "196") (name "unconnected-(U8-1Q-Pad9)") (class "Default")
      (node (ref "U8") (pin "9") (pinfunction "1Q_9") (pintype "unspecified"))
    )
    (net (code "197") (name "unconnected-(U8-2D-Pad2)") (class "Default")
      (node (ref "U8") (pin "2") (pinfunction "2D_2") (pintype "unspecified"))
    )
    (net (code "198") (name "unconnected-(U8-2Q-Pad10)") (class "Default")
      (node (ref "U8") (pin "10") (pinfunction "2Q_10") (pintype "unspecified"))
    )
    (net (code "199") (name "unconnected-(U8-3D-Pad3)") (class "Default")
      (node (ref "U8") (pin "3") (pinfunction "3D_3") (pintype "unspecified"))
    )
    (net (code "200") (name "unconnected-(U8-3Q-Pad11)") (class "Default")
      (node (ref "U8") (pin "11") (pinfunction "3Q_11") (pintype "unspecified"))
    )
    (net (code "201") (name "unconnected-(U8-4D-Pad4)") (class "Default")
      (node (ref "U8") (pin "4") (pinfunction "4D_4") (pintype "unspecified"))
    )
    (net (code "202") (name "unconnected-(U8-4Q-Pad12)") (class "Default")
      (node (ref "U8") (pin "12") (pinfunction "4Q_12") (pintype "unspecified"))
    )
    (net (code "203") (name "unconnected-(U8-5D-Pad5)") (class "Default")
      (node (ref "U8") (pin "5") (pinfunction "5D_5") (pintype "unspecified"))
    )
    (net (code "204") (name "unconnected-(U8-5Q-Pad16)") (class "Default")
      (node (ref "U8") (pin "16") (pinfunction "5Q_16") (pintype "unspecified"))
    )
    (net (code "205") (name "unconnected-(U8-6D-Pad6)") (class "Default")
      (node (ref "U8") (pin "6") (pinfunction "6D_6") (pintype "unspecified"))
    )
    (net (code "206") (name "unconnected-(U8-6Q-Pad13)") (class "Default")
      (node (ref "U8") (pin "13") (pinfunction "6Q_13") (pintype "unspecified"))
    )
    (net (code "207") (name "unconnected-(U8-7D-Pad7)") (class "Default")
      (node (ref "U8") (pin "7") (pinfunction "7D_7") (pintype "unspecified"))
    )
    (net (code "208") (name "unconnected-(U8-7Q-Pad14)") (class "Default")
      (node (ref "U8") (pin "14") (pinfunction "7Q_14") (pintype "unspecified"))
    )
    (net (code "209") (name "unconnected-(U8-8D-Pad8)") (class "Default")
      (node (ref "U8") (pin "8") (pinfunction "8D_8") (pintype "unspecified"))
    )
    (net (code "210") (name "unconnected-(U8-8Q-Pad15)") (class "Default")
      (node (ref "U8") (pin "15") (pinfunction "8Q_15") (pintype "unspecified"))
    )
    (net (code "211") (name "unconnected-(U8-G-Pad20)") (class "Default")
      (node (ref "U8") (pin "20") (pinfunction "G_20") (pintype "unspecified"))
    )
    (net (code "212") (name "unconnected-(U9-!OC-Pad21)") (class "Default")
      (node (ref "U9") (pin "21") (pinfunction "!OC_21") (pintype "unspecified"))
    )
    (net (code "213") (name "unconnected-(U9-1D-Pad1)") (class "Default")
      (node (ref "U9") (pin "1") (pinfunction "1D_1") (pintype "unspecified"))
    )
    (net (code "214") (name "unconnected-(U9-1Q-Pad9)") (class "Default")
      (node (ref "U9") (pin "9") (pinfunction "1Q_9") (pintype "unspecified"))
    )
    (net (code "215") (name "unconnected-(U9-2D-Pad2)") (class "Default")
      (node (ref "U9") (pin "2") (pinfunction "2D_2") (pintype "unspecified"))
    )
    (net (code "216") (name "unconnected-(U9-2Q-Pad10)") (class "Default")
      (node (ref "U9") (pin "10") (pinfunction "2Q_10") (pintype "unspecified"))
    )
    (net (code "217") (name "unconnected-(U9-3D-Pad3)") (class "Default")
      (node (ref "U9") (pin "3") (pinfunction "3D_3") (pintype "unspecified"))
    )
    (net (code "218") (name "unconnected-(U9-3Q-Pad11)") (class "Default")
      (node (ref "U9") (pin "11") (pinfunction "3Q_11") (pintype "unspecified"))
    )
    (net (code "219") (name "unconnected-(U9-4D-Pad4)") (class "Default")
      (node (ref "U9") (pin "4") (pinfunction "4D_4") (pintype "unspecified"))
    )
    (net (code "220") (name "unconnected-(U9-4Q-Pad12)") (class "Default")
      (node (ref "U9") (pin "12") (pinfunction "4Q_12") (pintype "unspecified"))
    )
    (net (code "221") (name "unconnected-(U9-5D-Pad5)") (class "Default")
      (node (ref "U9") (pin "5") (pinfunction "5D_5") (pintype "unspecified"))
    )
    (net (code "222") (name "unconnected-(U9-5Q-Pad16)") (class "Default")
      (node (ref "U9") (pin "16") (pinfunction "5Q_16") (pintype "unspecified"))
    )
    (net (code "223") (name "unconnected-(U9-6D-Pad6)") (class "Default")
      (node (ref "U9") (pin "6") (pinfunction "6D_6") (pintype "unspecified"))
    )
    (net (code "224") (name "unconnected-(U9-6Q-Pad13)") (class "Default")
      (node (ref "U9") (pin "13") (pinfunction "6Q_13") (pintype "unspecified"))
    )
    (net (code "225") (name "unconnected-(U9-7D-Pad7)") (class "Default")
      (node (ref "U9") (pin "7") (pinfunction "7D_7") (pintype "unspecified"))
    )
    (net (code "226") (name "unconnected-(U9-7Q-Pad14)") (class "Default")
      (node (ref "U9") (pin "14") (pinfunction "7Q_14") (pintype "unspecified"))
    )
    (net (code "227") (name "unconnected-(U9-8D-Pad8)") (class "Default")
      (node (ref "U9") (pin "8") (pinfunction "8D_8") (pintype "unspecified"))
    )
    (net (code "228") (name "unconnected-(U9-8Q-Pad15)") (class "Default")
      (node (ref "U9") (pin "15") (pinfunction "8Q_15") (pintype "unspecified"))
    )
    (net (code "229") (name "unconnected-(U9-G-Pad20)") (class "Default")
      (node (ref "U9") (pin "20") (pinfunction "G_20") (pintype "unspecified"))
    )
    (net (code "230") (name "unconnected-(U10-Pad1)") (class "Default")
      (node (ref "U10") (pin "1") (pinfunction "1_1") (pintype "unspecified"))
    )
    (net (code "231") (name "unconnected-(U10-Pad2)") (class "Default")
      (node (ref "U10") (pin "2") (pinfunction "2_2") (pintype "unspecified"))
    )
    (net (code "232") (name "unconnected-(U10-Pad3)") (class "Default")
      (node (ref "U10") (pin "3") (pinfunction "3_3") (pintype "unspecified"))
    )
    (net (code "233") (name "unconnected-(U10-Pad4)") (class "Default")
      (node (ref "U10") (pin "4") (pinfunction "4_4") (pintype "unspecified"))
    )
    (net (code "234") (name "unconnected-(U10-Pad5)") (class "Default")
      (node (ref "U10") (pin "5") (pinfunction "5_5") (pintype "unspecified"))
    )
    (net (code "235") (name "unconnected-(U10-Pad6)") (class "Default")
      (node (ref "U10") (pin "6") (pinfunction "6_6") (pintype "unspecified"))
    )
    (net (code "236") (name "unconnected-(U10-Pad7)") (class "Default")
      (node (ref "U10") (pin "7") (pinfunction "7_7") (pintype "unspecified"))
    )
    (net (code "237") (name "unconnected-(U10-Pad8)") (class "Default")
      (node (ref "U10") (pin "8") (pinfunction "8_8") (pintype "unspecified"))
    )
    (net (code "238") (name "unconnected-(U10-Pad9)") (class "Default")
      (node (ref "U10") (pin "9") (pinfunction "9_9") (pintype "unspecified"))
    )
    (net (code "239") (name "unconnected-(U10-Pad10)") (class "Default")
      (node (ref "U10") (pin "10") (pinfunction "10_10") (pintype "unspecified"))
    )
    (net (code "240") (name "unconnected-(U10-Pad11)") (class "Default")
      (node (ref "U10") (pin "11") (pinfunction "11_11") (pintype "unspecified"))
    )
    (net (code "241") (name "unconnected-(U10-Pad12)") (class "Default")
      (node (ref "U10") (pin "12") (pinfunction "12_12") (pintype "unspecified"))
    )
    (net (code "242") (name "unconnected-(U10-Pad13)") (class "Default")
      (node (ref "U10") (pin "13") (pinfunction "13_13") (pintype "unspecified"))
    )
    (net (code "243") (name "unconnected-(U10-Pad14)") (class "Default")
      (node (ref "U10") (pin "14") (pinfunction "14_14") (pintype "unspecified"))
    )
    (net (code "244") (name "unconnected-(U11-GND-Pad3)") (class "Default")
      (node (ref "U11") (pin "3") (pinfunction "GND_3") (pintype "passive"))
    )
    (net (code "245") (name "unconnected-(U11-IN_B-Pad1)") (class "Default")
      (node (ref "U11") (pin "1") (pinfunction "IN_B_1") (pintype "unspecified"))
    )
    (net (code "246") (name "unconnected-(U11-VDD-Pad5)") (class "Default")
      (node (ref "U11") (pin "5") (pinfunction "VDD_5") (pintype "passive"))
    )
    (net (code "247") (name "unconnected-(U11-Y-Pad4)") (class "Default")
      (node (ref "U11") (pin "4") (pinfunction "Y_4") (pintype "output"))
    )
    (net (code "248") (name "unconnected-(U12-GND-Pad3)") (class "Default")
      (node (ref "U12") (pin "3") (pinfunction "GND_3") (pintype "passive"))
    )
    (net (code "249") (name "unconnected-(U12-IN_A-Pad2)") (class "Default")
      (node (ref "U12") (pin "2") (pinfunction "IN_A_2") (pintype "unspecified"))
    )
    (net (code "250") (name "unconnected-(U12-Y-Pad4)") (class "Default")
      (node (ref "U12") (pin "4") (pinfunction "Y_4") (pintype "output"))
    )
    (net (code "251") (name "unconnected-(U13-!CS-Pad30)") (class "Default")
      (node (ref "U13") (pin "30") (pinfunction "!CS_30") (pintype "unspecified"))
    )
    (net (code "252") (name "unconnected-(U13-!OE-Pad31)") (class "Default")
      (node (ref "U13") (pin "31") (pinfunction "!OE_31") (pintype "unspecified"))
    )
    (net (code "253") (name "unconnected-(U13-!WE-Pad32)") (class "Default")
      (node (ref "U13") (pin "32") (pinfunction "!WE_32") (pintype "unspecified"))
    )
    (net (code "254") (name "unconnected-(U13-A0-Pad15)") (class "Default")
      (node (ref "U13") (pin "15") (pinfunction "A0_15") (pintype "unspecified"))
    )
    (net (code "255") (name "unconnected-(U13-A1-Pad16)") (class "Default")
      (node (ref "U13") (pin "16") (pinfunction "A1_16") (pintype "unspecified"))
    )
    (net (code "256") (name "unconnected-(U13-A2-Pad17)") (class "Default")
      (node (ref "U13") (pin "17") (pinfunction "A2_17") (pintype "unspecified"))
    )
    (net (code "257") (name "unconnected-(U13-A3-Pad18)") (class "Default")
      (node (ref "U13") (pin "18") (pinfunction "A3_18") (pintype "unspecified"))
    )
    (net (code "258") (name "unconnected-(U13-A4-Pad19)") (class "Default")
      (node (ref "U13") (pin "19") (pinfunction "A4_19") (pintype "unspecified"))
    )
    (net (code "259") (name "unconnected-(U13-A5-Pad20)") (class "Default")
      (node (ref "U13") (pin "20") (pinfunction "A5_20") (pintype "unspecified"))
    )
    (net (code "260") (name "unconnected-(U13-A6-Pad21)") (class "Default")
      (node (ref "U13") (pin "21") (pinfunction "A6_21") (pintype "unspecified"))
    )
    (net (code "261") (name "unconnected-(U13-A7-Pad22)") (class "Default")
      (node (ref "U13") (pin "22") (pinfunction "A7_22") (pintype "unspecified"))
    )
    (net (code "262") (name "unconnected-(U13-A8-Pad23)") (class "Default")
      (node (ref "U13") (pin "23") (pinfunction "A8_23") (pintype "unspecified"))
    )
    (net (code "263") (name "unconnected-(U13-A9-Pad24)") (class "Default")
      (node (ref "U13") (pin "24") (pinfunction "A9_24") (pintype "unspecified"))
    )
    (net (code "264") (name "unconnected-(U13-A10-Pad25)") (class "Default")
      (node (ref "U13") (pin "25") (pinfunction "A10_25") (pintype "unspecified"))
    )
    (net (code "265") (name "unconnected-(U13-A11-Pad26)") (class "Default")
      (node (ref "U13") (pin "26") (pinfunction "A11_26") (pintype "unspecified"))
    )
    (net (code "266") (name "unconnected-(U13-A12-Pad27)") (class "Default")
      (node (ref "U13") (pin "27") (pinfunction "A12_27") (pintype "unspecified"))
    )
    (net (code "267") (name "unconnected-(U13-A13-Pad28)") (class "Default")
      (node (ref "U13") (pin "28") (pinfunction "A13_28") (pintype "unspecified"))
    )
    (net (code "268") (name "unconnected-(U13-A14-Pad29)") (class "Default")
      (node (ref "U13") (pin "29") (pinfunction "A14_29") (pintype "unspecified"))
    )
    (net (code "269") (name "unconnected-(U13-I{slash}O0-Pad33)") (class "Default")
      (node (ref "U13") (pin "33") (pinfunction "I/O0_33") (pintype "unspecified"))
    )
    (net (code "270") (name "unconnected-(U13-I{slash}O1-Pad34)") (class "Default")
      (node (ref "U13") (pin "34") (pinfunction "I/O1_34") (pintype "unspecified"))
    )
    (net (code "271") (name "unconnected-(U13-I{slash}O2-Pad35)") (class "Default")
      (node (ref "U13") (pin "35") (pinfunction "I/O2_35") (pintype "unspecified"))
    )
    (net (code "272") (name "unconnected-(U13-I{slash}O3-Pad36)") (class "Default")
      (node (ref "U13") (pin "36") (pinfunction "I/O3_36") (pintype "unspecified"))
    )
    (net (code "273") (name "unconnected-(U13-I{slash}O4-Pad37)") (class "Default")
      (node (ref "U13") (pin "37") (pinfunction "I/O4_37") (pintype "unspecified"))
    )
    (net (code "274") (name "unconnected-(U13-I{slash}O5-Pad38)") (class "Default")
      (node (ref "U13") (pin "38") (pinfunction "I/O5_38") (pintype "unspecified"))
    )
    (net (code "275") (name "unconnected-(U13-I{slash}O6-Pad39)") (class "Default")
      (node (ref "U13") (pin "39") (pinfunction "I/O6_39") (pintype "unspecified"))
    )
    (net (code "276") (name "unconnected-(U13-I{slash}O7-Pad40)") (class "Default")
      (node (ref "U13") (pin "40") (pinfunction "I/O7_40") (pintype "unspecified"))
    )
    (net (code "277") (name "unconnected-(U14-!CS-Pad30)") (class "Default")
      (node (ref "U14") (pin "30") (pinfunction "!CS_30") (pintype "unspecified"))
    )
    (net (code "278") (name "unconnected-(U14-!OE-Pad31)") (class "Default")
      (node (ref "U14") (pin "31") (pinfunction "!OE_31") (pintype "unspecified"))
    )
    (net (code "279") (name "unconnected-(U14-!WE-Pad32)") (class "Default")
      (node (ref "U14") (pin "32") (pinfunction "!WE_32") (pintype "unspecified"))
    )
    (net (code "280") (name "unconnected-(U14-A0-Pad15)") (class "Default")
      (node (ref "U14") (pin "15") (pinfunction "A0_15") (pintype "unspecified"))
    )
    (net (code "281") (name "unconnected-(U14-A1-Pad16)") (class "Default")
      (node (ref "U14") (pin "16") (pinfunction "A1_16") (pintype "unspecified"))
    )
    (net (code "282") (name "unconnected-(U14-A2-Pad17)") (class "Default")
      (node (ref "U14") (pin "17") (pinfunction "A2_17") (pintype "unspecified"))
    )
    (net (code "283") (name "unconnected-(U14-A3-Pad18)") (class "Default")
      (node (ref "U14") (pin "18") (pinfunction "A3_18") (pintype "unspecified"))
    )
    (net (code "284") (name "unconnected-(U14-A4-Pad19)") (class "Default")
      (node (ref "U14") (pin "19") (pinfunction "A4_19") (pintype "unspecified"))
    )
    (net (code "285") (name "unconnected-(U14-A5-Pad20)") (class "Default")
      (node (ref "U14") (pin "20") (pinfunction "A5_20") (pintype "unspecified"))
    )
    (net (code "286") (name "unconnected-(U14-A6-Pad21)") (class "Default")
      (node (ref "U14") (pin "21") (pinfunction "A6_21") (pintype "unspecified"))
    )
    (net (code "287") (name "unconnected-(U14-A7-Pad22)") (class "Default")
      (node (ref "U14") (pin "22") (pinfunction "A7_22") (pintype "unspecified"))
    )
    (net (code "288") (name "unconnected-(U14-A8-Pad23)") (class "Default")
      (node (ref "U14") (pin "23") (pinfunction "A8_23") (pintype "unspecified"))
    )
    (net (code "289") (name "unconnected-(U14-A9-Pad24)") (class "Default")
      (node (ref "U14") (pin "24") (pinfunction "A9_24") (pintype "unspecified"))
    )
    (net (code "290") (name "unconnected-(U14-A10-Pad25)") (class "Default")
      (node (ref "U14") (pin "25") (pinfunction "A10_25") (pintype "unspecified"))
    )
    (net (code "291") (name "unconnected-(U14-A11-Pad26)") (class "Default")
      (node (ref "U14") (pin "26") (pinfunction "A11_26") (pintype "unspecified"))
    )
    (net (code "292") (name "unconnected-(U14-A12-Pad27)") (class "Default")
      (node (ref "U14") (pin "27") (pinfunction "A12_27") (pintype "unspecified"))
    )
    (net (code "293") (name "unconnected-(U14-A13-Pad28)") (class "Default")
      (node (ref "U14") (pin "28") (pinfunction "A13_28") (pintype "unspecified"))
    )
    (net (code "294") (name "unconnected-(U14-A14-Pad29)") (class "Default")
      (node (ref "U14") (pin "29") (pinfunction "A14_29") (pintype "unspecified"))
    )
    (net (code "295") (name "unconnected-(U14-I{slash}O0-Pad33)") (class "Default")
      (node (ref "U14") (pin "33") (pinfunction "I/O0_33") (pintype "unspecified"))
    )
    (net (code "296") (name "unconnected-(U14-I{slash}O1-Pad34)") (class "Default")
      (node (ref "U14") (pin "34") (pinfunction "I/O1_34") (pintype "unspecified"))
    )
    (net (code "297") (name "unconnected-(U14-I{slash}O2-Pad35)") (class "Default")
      (node (ref "U14") (pin "35") (pinfunction "I/O2_35") (pintype "unspecified"))
    )
    (net (code "298") (name "unconnected-(U14-I{slash}O3-Pad36)") (class "Default")
      (node (ref "U14") (pin "36") (pinfunction "I/O3_36") (pintype "unspecified"))
    )
    (net (code "299") (name "unconnected-(U14-I{slash}O4-Pad37)") (class "Default")
      (node (ref "U14") (pin "37") (pinfunction "I/O4_37") (pintype "unspecified"))
    )
    (net (code "300") (name "unconnected-(U14-I{slash}O5-Pad38)") (class "Default")
      (node (ref "U14") (pin "38") (pinfunction "I/O5_38") (pintype "unspecified"))
    )
    (net (code "301") (name "unconnected-(U14-I{slash}O6-Pad39)") (class "Default")
      (node (ref "U14") (pin "39") (pinfunction "I/O6_39") (pintype "unspecified"))
    )
    (net (code "302") (name "unconnected-(U14-I{slash}O7-Pad40)") (class "Default")
      (node (ref "U14") (pin "40") (pinfunction "I/O7_40") (pintype "unspecified"))
    )
    (net (code "303") (name "unconnected-(U15-Pad1)") (class "Default")
      (node (ref "U15") (pin "1") (pinfunction "1_1") (pintype "unspecified"))
    )
    (net (code "304") (name "unconnected-(U15-Pad2)") (class "Default")
      (node (ref "U15") (pin "2") (pinfunction "2_2") (pintype "unspecified"))
    )
    (net (code "305") (name "unconnected-(U15-Pad3)") (class "Default")
      (node (ref "U15") (pin "3") (pinfunction "3_3") (pintype "unspecified"))
    )
    (net (code "306") (name "unconnected-(U15-Pad4)") (class "Default")
      (node (ref "U15") (pin "4") (pinfunction "4_4") (pintype "unspecified"))
    )
    (net (code "307") (name "unconnected-(U15-Pad5)") (class "Default")
      (node (ref "U15") (pin "5") (pinfunction "5_5") (pintype "unspecified"))
    )
    (net (code "308") (name "unconnected-(U15-Pad6)") (class "Default")
      (node (ref "U15") (pin "6") (pinfunction "6_6") (pintype "unspecified"))
    )
    (net (code "309") (name "unconnected-(U15-Pad7)") (class "Default")
      (node (ref "U15") (pin "7") (pinfunction "7_7") (pintype "unspecified"))
    )
    (net (code "310") (name "unconnected-(U15-Pad8)") (class "Default")
      (node (ref "U15") (pin "8") (pinfunction "8_8") (pintype "unspecified"))
    )
    (net (code "311") (name "unconnected-(U15-Pad9)") (class "Default")
      (node (ref "U15") (pin "9") (pinfunction "9_9") (pintype "unspecified"))
    )
    (net (code "312") (name "unconnected-(U15-Pad10)") (class "Default")
      (node (ref "U15") (pin "10") (pinfunction "10_10") (pintype "unspecified"))
    )
    (net (code "313") (name "unconnected-(U15-Pad11)") (class "Default")
      (node (ref "U15") (pin "11") (pinfunction "11_11") (pintype "unspecified"))
    )
    (net (code "314") (name "unconnected-(U15-Pad12)") (class "Default")
      (node (ref "U15") (pin "12") (pinfunction "12_12") (pintype "unspecified"))
    )
    (net (code "315") (name "unconnected-(U15-Pad13)") (class "Default")
      (node (ref "U15") (pin "13") (pinfunction "13_13") (pintype "unspecified"))
    )
    (net (code "316") (name "unconnected-(U15-Pad14)") (class "Default")
      (node (ref "U15") (pin "14") (pinfunction "14_14") (pintype "unspecified"))
    )
    (net (code "317") (name "unconnected-(U16-Pad1)") (class "Default")
      (node (ref "U16") (pin "1") (pinfunction "1_1") (pintype "unspecified"))
    )
    (net (code "318") (name "unconnected-(U16-Pad2)") (class "Default")
      (node (ref "U16") (pin "2") (pinfunction "2_2") (pintype "unspecified"))
    )
    (net (code "319") (name "unconnected-(U16-Pad3)") (class "Default")
      (node (ref "U16") (pin "3") (pinfunction "3_3") (pintype "unspecified"))
    )
    (net (code "320") (name "unconnected-(U16-Pad4)") (class "Default")
      (node (ref "U16") (pin "4") (pinfunction "4_4") (pintype "unspecified"))
    )
    (net (code "321") (name "unconnected-(U16-Pad5)") (class "Default")
      (node (ref "U16") (pin "5") (pinfunction "5_5") (pintype "unspecified"))
    )
    (net (code "322") (name "unconnected-(U16-Pad6)") (class "Default")
      (node (ref "U16") (pin "6") (pinfunction "6_6") (pintype "unspecified"))
    )
    (net (code "323") (name "unconnected-(U16-Pad7)") (class "Default")
      (node (ref "U16") (pin "7") (pinfunction "7_7") (pintype "unspecified"))
    )
    (net (code "324") (name "unconnected-(U16-Pad8)") (class "Default")
      (node (ref "U16") (pin "8") (pinfunction "8_8") (pintype "unspecified"))
    )
    (net (code "325") (name "unconnected-(U16-Pad9)") (class "Default")
      (node (ref "U16") (pin "9") (pinfunction "9_9") (pintype "unspecified"))
    )
    (net (code "326") (name "unconnected-(U16-Pad10)") (class "Default")
      (node (ref "U16") (pin "10") (pinfunction "10_10") (pintype "unspecified"))
    )
    (net (code "327") (name "unconnected-(U16-Pad11)") (class "Default")
      (node (ref "U16") (pin "11") (pinfunction "11_11") (pintype "unspecified"))
    )
    (net (code "328") (name "unconnected-(U16-Pad12)") (class "Default")
      (node (ref "U16") (pin "12") (pinfunction "12_12") (pintype "unspecified"))
    )
    (net (code "329") (name "unconnected-(U16-Pad13)") (class "Default")
      (node (ref "U16") (pin "13") (pinfunction "13_13") (pintype "unspecified"))
    )
    (net (code "330") (name "unconnected-(U16-Pad14)") (class "Default")
      (node (ref "U16") (pin "14") (pinfunction "14_14") (pintype "unspecified"))
    )
    (net (code "331") (name "unconnected-(U17-GND-Pad3)") (class "Default")
      (node (ref "U17") (pin "3") (pinfunction "GND_3") (pintype "passive"))
    )
    (net (code "332") (name "unconnected-(U17-OUT_Y-Pad4)") (class "Default")
      (node (ref "U17") (pin "4") (pinfunction "OUT_Y_4") (pintype "output"))
    )
    (net (code "333") (name "unconnected-(U17-VCC-Pad5)") (class "Default")
      (node (ref "U17") (pin "5") (pinfunction "VCC_5") (pintype "passive"))
    )
    (net (code "334") (name "unconnected-(U18-GND-Pad3)") (class "Default")
      (node (ref "U18") (pin "3") (pinfunction "GND_3") (pintype "passive"))
    )
    (net (code "335") (name "unconnected-(U18-IN_B-Pad1)") (class "Default")
      (node (ref "U18") (pin "1") (pinfunction "IN_B_1") (pintype "unspecified"))
    )
    (net (code "336") (name "unconnected-(U18-VCC-Pad5)") (class "Default")
      (node (ref "U18") (pin "5") (pinfunction "VCC_5") (pintype "passive"))
    )
    (net (code "337") (name "unconnected-(U19-GND-Pad3)") (class "Default")
      (node (ref "U19") (pin "3") (pinfunction "GND_3") (pintype "passive"))
    )
    (net (code "338") (name "unconnected-(U19-IN_B-Pad1)") (class "Default")
      (node (ref "U19") (pin "1") (pinfunction "IN_B_1") (pintype "unspecified"))
    )
    (net (code "339") (name "unconnected-(U20-GND-Pad3)") (class "Default")
      (node (ref "U20") (pin "3") (pinfunction "GND_3") (pintype "passive"))
    )
    (net (code "340") (name "unconnected-(U20-IN_B-Pad1)") (class "Default")
      (node (ref "U20") (pin "1") (pinfunction "IN_B_1") (pintype "unspecified"))
    )
    (net (code "341") (name "unconnected-(U21-GND-Pad3)") (class "Default")
      (node (ref "U21") (pin "3") (pinfunction "GND_3") (pintype "passive"))
    )
    (net (code "342") (name "unconnected-(U21-IN_A-Pad2)") (class "Default")
      (node (ref "U21") (pin "2") (pinfunction "IN_A_2") (pintype "unspecified"))
    )
    (net (code "343") (name "unconnected-(U21-IN_B-Pad1)") (class "Default")
      (node (ref "U21") (pin "1") (pinfunction "IN_B_1") (pintype "unspecified"))
    )
    (net (code "344") (name "unconnected-(U22-GND-Pad3)") (class "Default")
      (node (ref "U22") (pin "3") (pinfunction "GND_3") (pintype "passive"))
    )
    (net (code "345") (name "unconnected-(U22-VDD-Pad5)") (class "Default")
      (node (ref "U22") (pin "5") (pinfunction "VDD_5") (pintype "passive"))
    )
    (net (code "346") (name "unconnected-(U23-GND-Pad3)") (class "Default")
      (node (ref "U23") (pin "3") (pinfunction "GND_3") (pintype "passive"))
    )
    (net (code "347") (name "unconnected-(U23-IN_A-Pad2)") (class "Default")
      (node (ref "U23") (pin "2") (pinfunction "IN_A_2") (pintype "unspecified"))
    )
    (net (code "348") (name "unconnected-(U23-VDD-Pad5)") (class "Default")
      (node (ref "U23") (pin "5") (pinfunction "VDD_5") (pintype "passive"))
    )
    (net (code "349") (name "unconnected-(U23-Y-Pad4)") (class "Default")
      (node (ref "U23") (pin "4") (pinfunction "Y_4") (pintype "output"))
    )
    (net (code "350") (name "unconnected-(U25-IN-Pad1)") (class "Default")
      (node (ref "U25") (pin "1") (pinfunction "IN_1") (pintype "unspecified"))
    )
    (net (code "351") (name "unconnected-(U25-OUT-Pad2)") (class "Default")
      (node (ref "U25") (pin "2") (pinfunction "OUT_2") (pintype "unspecified"))
    )
    (net (code "352") (name "unconnected-(U26-IN-Pad1)") (class "Default")
      (node (ref "U26") (pin "1") (pinfunction "IN_1") (pintype "unspecified"))
    )
    (net (code "353") (name "unconnected-(U26-OUT-Pad2)") (class "Default")
      (node (ref "U26") (pin "2") (pinfunction "OUT_2") (pintype "unspecified"))
    )
    (net (code "354") (name "unconnected-(U27-IN-Pad1)") (class "Default")
      (node (ref "U27") (pin "1") (pinfunction "IN_1") (pintype "unspecified"))
    )
    (net (code "355") (name "unconnected-(U27-OUT-Pad2)") (class "Default")
      (node (ref "U27") (pin "2") (pinfunction "OUT_2") (pintype "unspecified"))
    )
    (net (code "356") (name "unconnected-(U28-IN-Pad1)") (class "Default")
      (node (ref "U28") (pin "1") (pinfunction "IN_1") (pintype "unspecified"))
    )
    (net (code "357") (name "unconnected-(U28-OUT-Pad2)") (class "Default")
      (node (ref "U28") (pin "2") (pinfunction "OUT_2") (pintype "unspecified"))
    )
    (net (code "358") (name "unconnected-(U29-IN-Pad1)") (class "Default")
      (node (ref "U29") (pin "1") (pinfunction "IN_1") (pintype "unspecified"))
    )
    (net (code "359") (name "unconnected-(U29-OUT-Pad2)") (class "Default")
      (node (ref "U29") (pin "2") (pinfunction "OUT_2") (pintype "unspecified"))
    )
    (net (code "360") (name "unconnected-(U30-!CS-Pad20)") (class "Default")
      (node (ref "U30") (pin "20") (pinfunction "!CS_20") (pintype "unspecified"))
    )
    (net (code "361") (name "unconnected-(U30-!CTS-Pad26)") (class "Default")
      (node (ref "U30") (pin "26") (pinfunction "!CTS_26") (pintype "unspecified"))
    )
    (net (code "362") (name "unconnected-(U30-!RD-Pad21)") (class "Default")
      (node (ref "U30") (pin "21") (pinfunction "!RD_21") (pintype "unspecified"))
    )
    (net (code "363") (name "unconnected-(U30-!RxC-Pad24)") (class "Default")
      (node (ref "U30") (pin "24") (pinfunction "!RxC_24") (pintype "unspecified"))
    )
    (net (code "364") (name "unconnected-(U30-!TxC-Pad25)") (class "Default")
      (node (ref "U30") (pin "25") (pinfunction "!TxC_25") (pintype "unspecified"))
    )
    (net (code "365") (name "unconnected-(U30-!WR-Pad30)") (class "Default")
      (node (ref "U30") (pin "30") (pinfunction "!WR_30") (pintype "unspecified"))
    )
    (net (code "366") (name "unconnected-(U30-CLK-Pad32)") (class "Default")
      (node (ref "U30") (pin "32") (pinfunction "CLK_32") (pintype "unspecified"))
    )
    (net (code "367") (name "unconnected-(U30-C{slash}!D-Pad31)") (class "Default")
      (node (ref "U30") (pin "31") (pinfunction "C/!D_31") (pintype "unspecified"))
    )
    (net (code "368") (name "unconnected-(U30-D0-Pad9)") (class "Default")
      (node (ref "U30") (pin "9") (pinfunction "D0_9") (pintype "unspecified"))
    )
    (net (code "369") (name "unconnected-(U30-D1-Pad15)") (class "Default")
      (node (ref "U30") (pin "15") (pinfunction "D1_15") (pintype "unspecified"))
    )
    (net (code "370") (name "unconnected-(U30-D2-Pad14)") (class "Default")
      (node (ref "U30") (pin "14") (pinfunction "D2_14") (pintype "unspecified"))
    )
    (net (code "371") (name "unconnected-(U30-D3-Pad13)") (class "Default")
      (node (ref "U30") (pin "13") (pinfunction "D3_13") (pintype "unspecified"))
    )
    (net (code "372") (name "unconnected-(U30-D4-Pad16)") (class "Default")
      (node (ref "U30") (pin "16") (pinfunction "D4_16") (pintype "unspecified"))
    )
    (net (code "373") (name "unconnected-(U30-D5-Pad12)") (class "Default")
      (node (ref "U30") (pin "12") (pinfunction "D5_12") (pintype "unspecified"))
    )
    (net (code "374") (name "unconnected-(U30-D6-Pad11)") (class "Default")
      (node (ref "U30") (pin "11") (pinfunction "D6_11") (pintype "unspecified"))
    )
    (net (code "375") (name "unconnected-(U30-D7-Pad10)") (class "Default")
      (node (ref "U30") (pin "10") (pinfunction "D7_10") (pintype "unspecified"))
    )
    (net (code "376") (name "unconnected-(U30-RESET-Pad33)") (class "Default")
      (node (ref "U30") (pin "33") (pinfunction "RESET_33") (pintype "unspecified"))
    )
    (net (code "377") (name "unconnected-(U30-RxD-Pad22)") (class "Default")
      (node (ref "U30") (pin "22") (pinfunction "RxD_22") (pintype "unspecified"))
    )
    (net (code "378") (name "unconnected-(U30-TxD-Pad23)") (class "Default")
      (node (ref "U30") (pin "23") (pinfunction "TxD_23") (pintype "unspecified"))
    )
    (net (code "379") (name "unconnected-(U31-!CS-Pad20)") (class "Default")
      (node (ref "U31") (pin "20") (pinfunction "!CS_20") (pintype "unspecified"))
    )
    (net (code "380") (name "unconnected-(U31-!RD-Pad30)") (class "Default")
      (node (ref "U31") (pin "30") (pinfunction "!RD_30") (pintype "unspecified"))
    )
    (net (code "381") (name "unconnected-(U31-!WR-Pad39)") (class "Default")
      (node (ref "U31") (pin "39") (pinfunction "!WR_39") (pintype "unspecified"))
    )
    (net (code "382") (name "unconnected-(U31-A0-Pad31)") (class "Default")
      (node (ref "U31") (pin "31") (pinfunction "A0_31") (pintype "unspecified"))
    )
    (net (code "383") (name "unconnected-(U31-A1-Pad32)") (class "Default")
      (node (ref "U31") (pin "32") (pinfunction "A1_32") (pintype "unspecified"))
    )
    (net (code "384") (name "unconnected-(U31-D0-Pad9)") (class "Default")
      (node (ref "U31") (pin "9") (pinfunction "D0_9") (pintype "unspecified"))
    )
    (net (code "385") (name "unconnected-(U31-D1-Pad15)") (class "Default")
      (node (ref "U31") (pin "15") (pinfunction "D1_15") (pintype "unspecified"))
    )
    (net (code "386") (name "unconnected-(U31-D2-Pad14)") (class "Default")
      (node (ref "U31") (pin "14") (pinfunction "D2_14") (pintype "unspecified"))
    )
    (net (code "387") (name "unconnected-(U31-D3-Pad13)") (class "Default")
      (node (ref "U31") (pin "13") (pinfunction "D3_13") (pintype "unspecified"))
    )
    (net (code "388") (name "unconnected-(U31-D4-Pad16)") (class "Default")
      (node (ref "U31") (pin "16") (pinfunction "D4_16") (pintype "unspecified"))
    )
    (net (code "389") (name "unconnected-(U31-D5-Pad12)") (class "Default")
      (node (ref "U31") (pin "12") (pinfunction "D5_12") (pintype "unspecified"))
    )
    (net (code "390") (name "unconnected-(U31-D6-Pad11)") (class "Default")
      (node (ref "U31") (pin "11") (pinfunction "D6_11") (pintype "unspecified"))
    )
    (net (code "391") (name "unconnected-(U31-D7-Pad10)") (class "Default")
      (node (ref "U31") (pin "10") (pinfunction "D7_10") (pintype "unspecified"))
    )
    (net (code "392") (name "unconnected-(U31-PA0-Pad27)") (class "Default")
      (node (ref "U31") (pin "27") (pinfunction "PA0_27") (pintype "unspecified"))
    )
    (net (code "393") (name "unconnected-(U31-PA1-Pad26)") (class "Default")
      (node (ref "U31") (pin "26") (pinfunction "PA1_26") (pintype "unspecified"))
    )
    (net (code "394") (name "unconnected-(U31-PA2-Pad25)") (class "Default")
      (node (ref "U31") (pin "25") (pinfunction "PA2_25") (pintype "unspecified"))
    )
    (net (code "395") (name "unconnected-(U31-PA3-Pad24)") (class "Default")
      (node (ref "U31") (pin "24") (pinfunction "PA3_24") (pintype "unspecified"))
    )
    (net (code "396") (name "unconnected-(U31-PA4-Pad23)") (class "Default")
      (node (ref "U31") (pin "23") (pinfunction "PA4_23") (pintype "unspecified"))
    )
    (net (code "397") (name "unconnected-(U31-PA5-Pad22)") (class "Default")
      (node (ref "U31") (pin "22") (pinfunction "PA5_22") (pintype "unspecified"))
    )
    (net (code "398") (name "unconnected-(U31-PA6-Pad21)") (class "Default")
      (node (ref "U31") (pin "21") (pinfunction "PA6_21") (pintype "unspecified"))
    )
    (net (code "399") (name "unconnected-(U31-PA7-Pad19)") (class "Default")
      (node (ref "U31") (pin "19") (pinfunction "PA7_19") (pintype "unspecified"))
    )
    (net (code "400") (name "unconnected-(U31-PB0-Pad40)") (class "Default")
      (node (ref "U31") (pin "40") (pinfunction "PB0_40") (pintype "unspecified"))
    )
    (net (code "401") (name "unconnected-(U31-PC0-Pad41)") (class "Default")
      (node (ref "U31") (pin "41") (pinfunction "PC0_41") (pintype "unspecified"))
    )
    (net (code "402") (name "unconnected-(U31-RESET-Pad33)") (class "Default")
      (node (ref "U31") (pin "33") (pinfunction "RESET_33") (pintype "unspecified"))
    )
    (net (code "403") (name "unconnected-(U32-GND-Pad3)") (class "Default")
      (node (ref "U32") (pin "3") (pinfunction "GND_3") (pintype "passive"))
    )
    (net (code "404") (name "unconnected-(U32-OUT_Y-Pad4)") (class "Default")
      (node (ref "U32") (pin "4") (pinfunction "OUT_Y_4") (pintype "output"))
    )
    (net (code "405") (name "unconnected-(U32-VCC-Pad5)") (class "Default")
      (node (ref "U32") (pin "5") (pinfunction "VCC_5") (pintype "passive"))
    )
    (net (code "406") (name "unconnected-(U33-GND-Pad3)") (class "Default")
      (node (ref "U33") (pin "3") (pinfunction "GND_3") (pintype "passive"))
    )
    (net (code "407") (name "unconnected-(U33-OUT_Y-Pad4)") (class "Default")
      (node (ref "U33") (pin "4") (pinfunction "OUT_Y_4") (pintype "output"))
    )
    (net (code "408") (name "unconnected-(U33-VCC-Pad5)") (class "Default")
      (node (ref "U33") (pin "5") (pinfunction "VCC_5") (pintype "passive"))
    )
    (net (code "409") (name "unconnected-(U34-GND-Pad3)") (class "Default")
      (node (ref "U34") (pin "3") (pinfunction "GND_3") (pintype "passive"))
    )
    (net (code "410") (name "unconnected-(U34-OUT_Y-Pad4)") (class "Default")
      (node (ref "U34") (pin "4") (pinfunction "OUT_Y_4") (pintype "output"))
    )
    (net (code "411") (name "unconnected-(U34-VCC-Pad5)") (class "Default")
      (node (ref "U34") (pin "5") (pinfunction "VCC_5") (pintype "passive"))
    )
    (net (code "412") (name "unconnected-(U35-GND-Pad3)") (class "Default")
      (node (ref "U35") (pin "3") (pinfunction "GND_3") (pintype "passive"))
    )
    (net (code "413") (name "unconnected-(U35-OUT_Y-Pad4)") (class "Default")
      (node (ref "U35") (pin "4") (pinfunction "OUT_Y_4") (pintype "output"))
    )
    (net (code "414") (name "unconnected-(U35-VCC-Pad5)") (class "Default")
      (node (ref "U35") (pin "5") (pinfunction "VCC_5") (pintype "passive"))
    )
    (net (code "415") (name "unconnected-(U36-GND-Pad3)") (class "Default")
      (node (ref "U36") (pin "3") (pinfunction "GND_3") (pintype "passive"))
    )
    (net (code "416") (name "unconnected-(U36-OUT_Y-Pad4)") (class "Default")
      (node (ref "U36") (pin "4") (pinfunction "OUT_Y_4") (pintype "output"))
    )
    (net (code "417") (name "unconnected-(U36-VCC-Pad5)") (class "Default")
      (node (ref "U36") (pin "5") (pinfunction "VCC_5") (pintype "passive"))
    )
    (net (code "418") (name "unconnected-(U37-GND-Pad3)") (class "Default")
      (node (ref "U37") (pin "3") (pinfunction "GND_3") (pintype "passive"))
    )
    (net (code "419") (name "unconnected-(U37-OUT_Y-Pad4)") (class "Default")
      (node (ref "U37") (pin "4") (pinfunction "OUT_Y_4") (pintype "output"))
    )
    (net (code "420") (name "unconnected-(U37-VCC-Pad5)") (class "Default")
      (node (ref "U37") (pin "5") (pinfunction "VCC_5") (pintype "passive"))
    )
    (net (code "421") (name "unconnected-(U38-GND-Pad3)") (class "Default")
      (node (ref "U38") (pin "3") (pinfunction "GND_3") (pintype "passive"))
    )
    (net (code "422") (name "unconnected-(U38-OUT_Y-Pad4)") (class "Default")
      (node (ref "U38") (pin "4") (pinfunction "OUT_Y_4") (pintype "output"))
    )
    (net (code "423") (name "unconnected-(U38-VCC-Pad5)") (class "Default")
      (node (ref "U38") (pin "5") (pinfunction "VCC_5") (pintype "passive"))
    )
    (net (code "424") (name "unconnected-(U39-OUT_Y-Pad4)") (class "Default")
      (node (ref "U39") (pin "4") (pinfunction "OUT_Y_4") (pintype "output"))
    )
    (net (code "425") (name "unconnected-(U40-GND-Pad3)") (class "Default")
      (node (ref "U40") (pin "3") (pinfunction "GND_3") (pintype "passive"))
    )
    (net (code "426") (name "unconnected-(U40-OUT_Y-Pad4)") (class "Default")
      (node (ref "U40") (pin "4") (pinfunction "OUT_Y_4") (pintype "output"))
    )
    (net (code "427") (name "unconnected-(U40-VCC-Pad5)") (class "Default")
      (node (ref "U40") (pin "5") (pinfunction "VCC_5") (pintype "passive"))
    )
    (net (code "428") (name "unconnected-(U41-OUT_Y-Pad4)") (class "Default")
      (node (ref "U41") (pin "4") (pinfunction "OUT_Y_4") (pintype "output"))
    )
  )
)
